# tdt_rereference.net
KiCad netlist of a schematic drawn in EAGLE
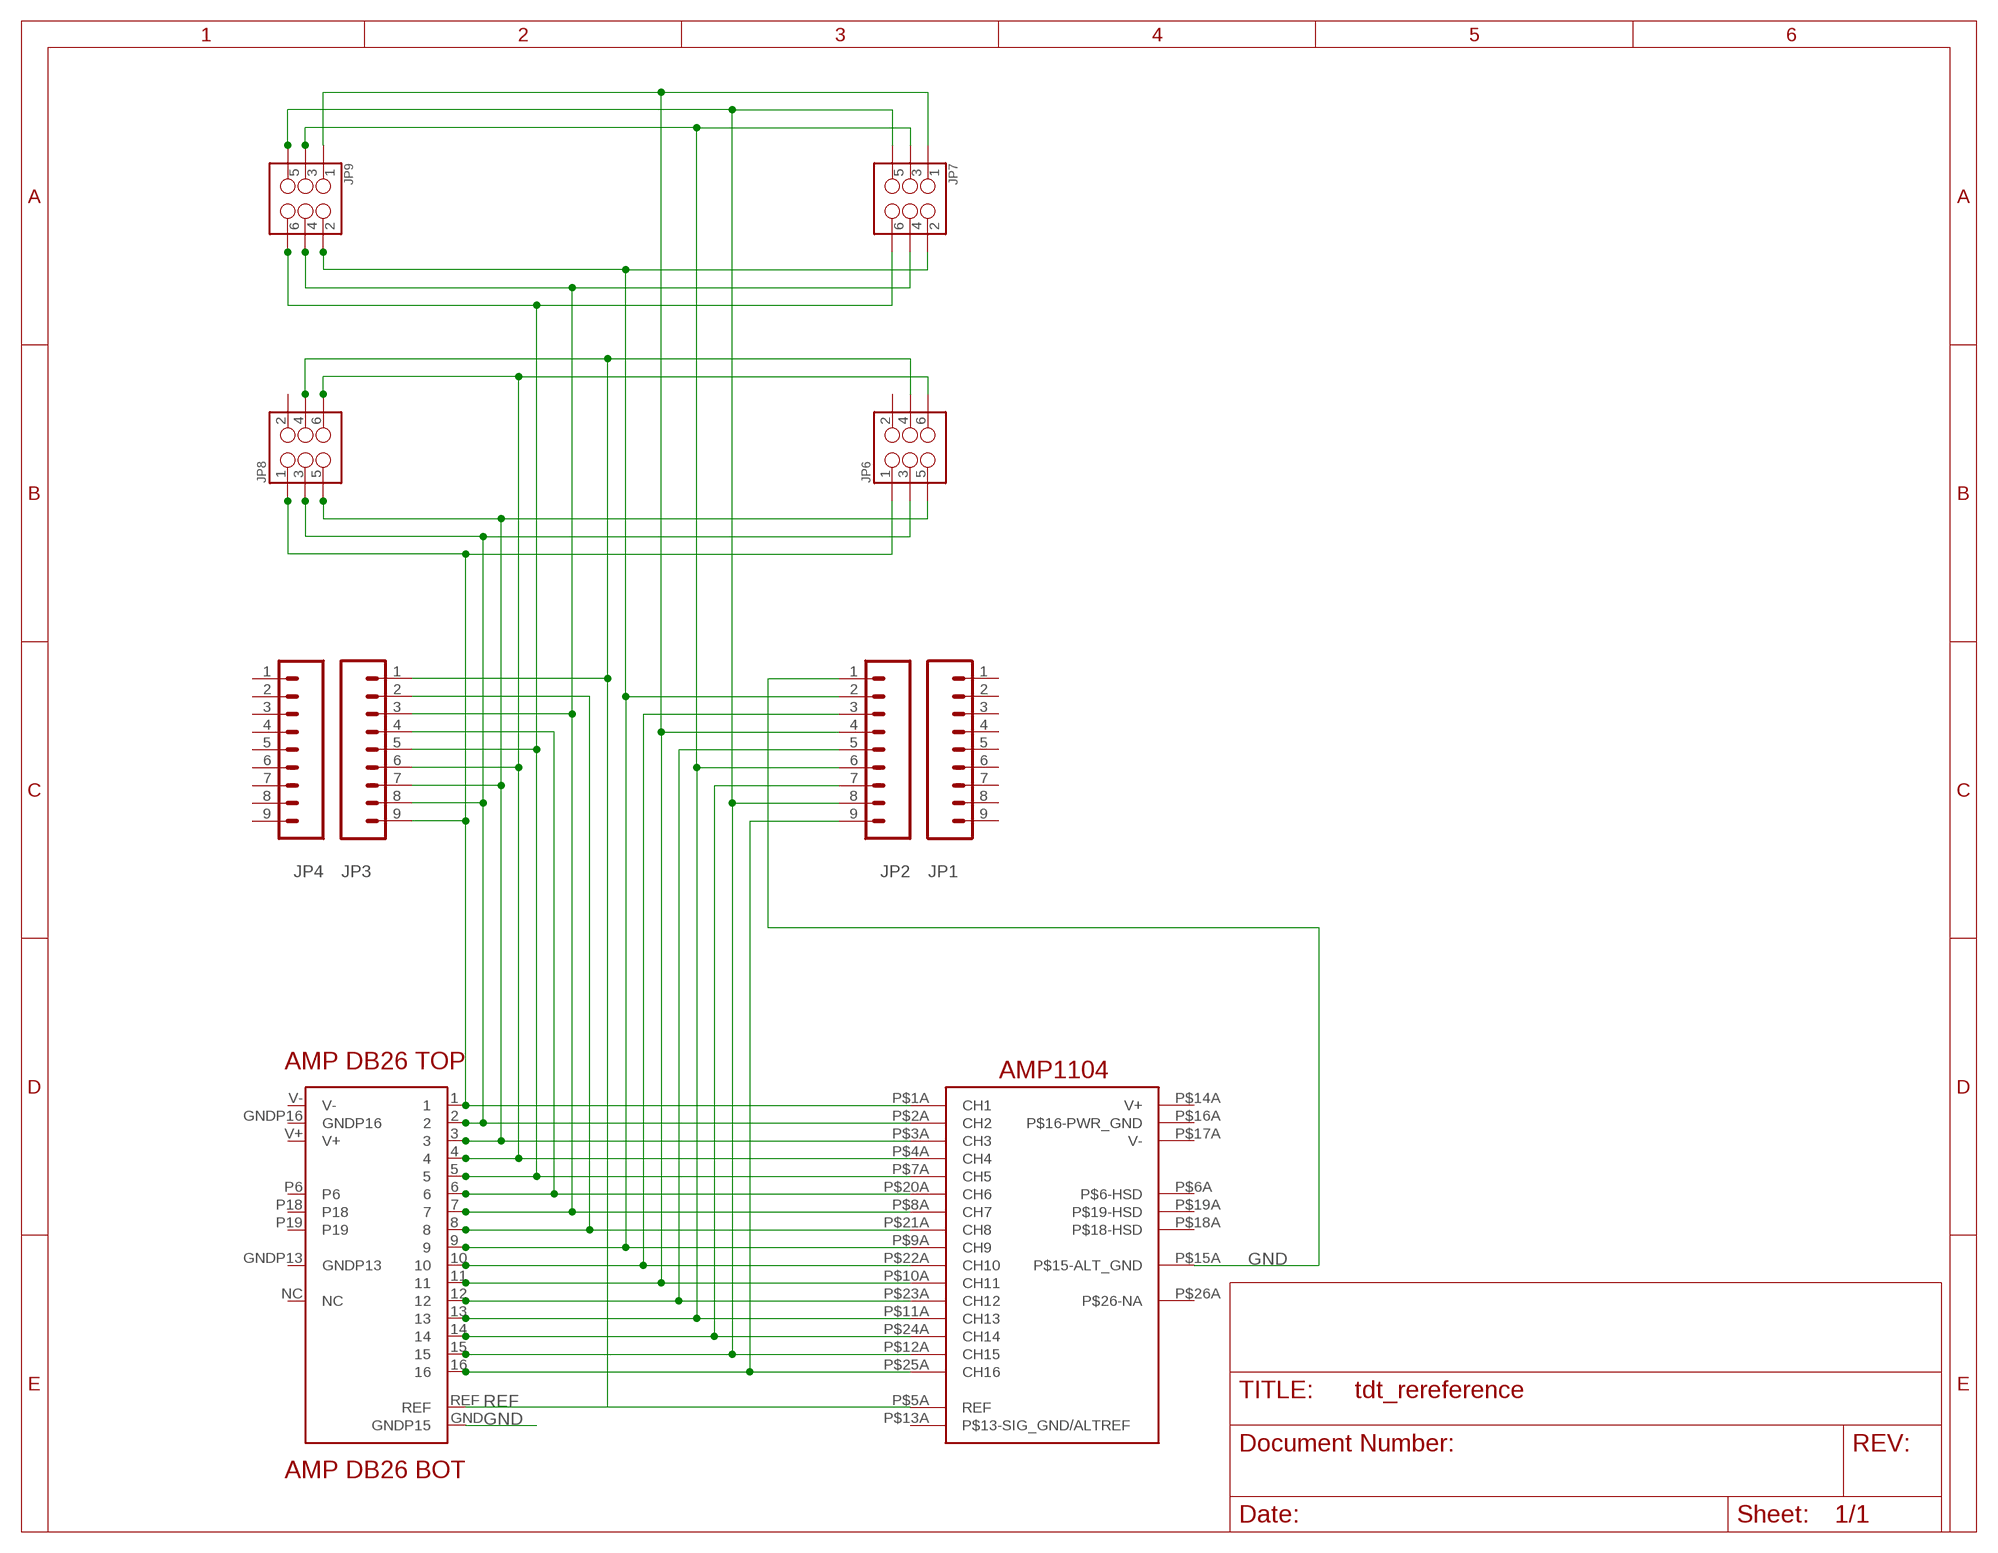
[diagram p0: schematic, sheet 1]

(export (version "E")
  (design (tool "Eeschema 10.0.6"))
  (components
    (comp (ref "JP1")
      (value "M09")
      (footprint "eagle-import:1X09")
      (libsource (lib "eagle-import") (part "M09"))
    )
    (comp (ref "JP2")
      (value "M09")
      (footprint "eagle-import:1X09")
      (libsource (lib "eagle-import") (part "M09"))
    )
    (comp (ref "JP3")
      (value "M09")
      (footprint "eagle-import:1X09")
      (libsource (lib "eagle-import") (part "M09"))
    )
    (comp (ref "JP4")
      (value "M09")
      (footprint "eagle-import:1X09")
      (libsource (lib "eagle-import") (part "M09"))
    )
    (comp (ref "JP6")
      (value "M03X22X3_SILK_MALE_PTH")
      (footprint "eagle-import:2X3")
      (libsource (lib "eagle-import") (part "M03X22X3_SILK_MALE_PTH"))
    )
    (comp (ref "JP7")
      (value "M03X22X3_SILK_MALE_PTH")
      (footprint "eagle-import:2X3")
      (libsource (lib "eagle-import") (part "M03X22X3_SILK_MALE_PTH"))
    )
    (comp (ref "JP8")
      (value "M03X22X3_SILK_MALE_PTH")
      (footprint "eagle-import:2X3")
      (libsource (lib "eagle-import") (part "M03X22X3_SILK_MALE_PTH"))
    )
    (comp (ref "JP9")
      (value "M03X22X3_SILK_MALE_PTH")
      (footprint "eagle-import:2X3")
      (libsource (lib "eagle-import") (part "M03X22X3_SILK_MALE_PTH"))
    )
    (comp (ref "U$1")
      (value "DB26-MALE-BOT")
      (footprint "eagle-import:DB26-MALE-BOT")
      (libsource (lib "eagle-import") (part "DB26-MALE-BOT"))
    )
    (comp (ref "U$2")
      (value "DB26-MALE-TOP")
      (footprint "eagle-import:DB26-MALE-TOP")
      (libsource (lib "eagle-import") (part "DB26-MALE-TOP"))
    )
    (comp (ref "U$3")
      (value "AMP1104")
      (footprint "eagle-import:AMP1104")
      (libsource (lib "eagle-import") (part "AMP1104"))
    )
  )
  (nets
    (net (code "1") (name "/GND") (class "Default")
      (node (ref "JP2") (pin "1") (pinfunction "1_1") (pintype "passive"))
      (node (ref "U$1") (pin "GND") (pinfunction "GNDP15_GND") (pintype "bidirectional"))
      (node (ref "U$3") (pin "P$15A") (pinfunction "P$15-ALT_GND_P$15A") (pintype "bidirectional"))
    )
    (net (code "2") (name "/REF") (class "Default")
      (node (ref "JP3") (pin "1") (pinfunction "1_1") (pintype "passive"))
      (node (ref "JP6") (pin "4") (pinfunction "4_4") (pintype "bidirectional"))
      (node (ref "JP8") (pin "4") (pinfunction "4_4") (pintype "bidirectional"))
      (node (ref "U$2") (pin "REF") (pinfunction "REF_REF") (pintype "bidirectional"))
      (node (ref "U$3") (pin "P$5A") (pinfunction "REF_P$5A") (pintype "bidirectional"))
    )
    (net (code "3") (name "Net-(U$3-CH1)") (class "Default")
      (node (ref "JP3") (pin "9") (pinfunction "9_9") (pintype "passive"))
      (node (ref "JP6") (pin "1") (pinfunction "1_1") (pintype "bidirectional"))
      (node (ref "JP8") (pin "1") (pinfunction "1_1") (pintype "bidirectional"))
      (node (ref "U$2") (pin "1") (pinfunction "1_1") (pintype "bidirectional"))
      (node (ref "U$3") (pin "P$1A") (pinfunction "CH1_P$1A") (pintype "bidirectional"))
    )
    (net (code "4") (name "Net-(U$3-CH2)") (class "Default")
      (node (ref "JP3") (pin "8") (pinfunction "8_8") (pintype "passive"))
      (node (ref "JP6") (pin "3") (pinfunction "3_3") (pintype "bidirectional"))
      (node (ref "JP8") (pin "3") (pinfunction "3_3") (pintype "bidirectional"))
      (node (ref "U$2") (pin "2") (pinfunction "2_2") (pintype "bidirectional"))
      (node (ref "U$3") (pin "P$2A") (pinfunction "CH2_P$2A") (pintype "bidirectional"))
    )
    (net (code "5") (name "Net-(U$3-CH3)") (class "Default")
      (node (ref "JP3") (pin "7") (pinfunction "7_7") (pintype "passive"))
      (node (ref "JP6") (pin "5") (pinfunction "5_5") (pintype "bidirectional"))
      (node (ref "JP8") (pin "5") (pinfunction "5_5") (pintype "bidirectional"))
      (node (ref "U$2") (pin "3") (pinfunction "3_3") (pintype "bidirectional"))
      (node (ref "U$3") (pin "P$3A") (pinfunction "CH3_P$3A") (pintype "bidirectional"))
    )
    (net (code "6") (name "Net-(U$3-CH4)") (class "Default")
      (node (ref "JP3") (pin "6") (pinfunction "6_6") (pintype "passive"))
      (node (ref "JP6") (pin "6") (pinfunction "6_6") (pintype "bidirectional"))
      (node (ref "JP8") (pin "6") (pinfunction "6_6") (pintype "bidirectional"))
      (node (ref "U$2") (pin "4") (pinfunction "4_4") (pintype "bidirectional"))
      (node (ref "U$3") (pin "P$4A") (pinfunction "CH4_P$4A") (pintype "bidirectional"))
    )
    (net (code "7") (name "Net-(U$3-CH5)") (class "Default")
      (node (ref "JP3") (pin "5") (pinfunction "5_5") (pintype "passive"))
      (node (ref "JP7") (pin "6") (pinfunction "6_6") (pintype "bidirectional"))
      (node (ref "JP9") (pin "6") (pinfunction "6_6") (pintype "bidirectional"))
      (node (ref "U$2") (pin "5") (pinfunction "5_5") (pintype "bidirectional"))
      (node (ref "U$3") (pin "P$7A") (pinfunction "CH5_P$7A") (pintype "bidirectional"))
    )
    (net (code "8") (name "Net-(U$3-CH6)") (class "Default")
      (node (ref "JP3") (pin "4") (pinfunction "4_4") (pintype "passive"))
      (node (ref "U$1") (pin "6") (pinfunction "6_6") (pintype "bidirectional"))
      (node (ref "U$3") (pin "P$20A") (pinfunction "CH6_P$20A") (pintype "bidirectional"))
    )
    (net (code "9") (name "Net-(U$3-CH7)") (class "Default")
      (node (ref "JP3") (pin "3") (pinfunction "3_3") (pintype "passive"))
      (node (ref "JP7") (pin "4") (pinfunction "4_4") (pintype "bidirectional"))
      (node (ref "JP9") (pin "4") (pinfunction "4_4") (pintype "bidirectional"))
      (node (ref "U$2") (pin "7") (pinfunction "7_7") (pintype "bidirectional"))
      (node (ref "U$3") (pin "P$8A") (pinfunction "CH7_P$8A") (pintype "bidirectional"))
    )
    (net (code "10") (name "Net-(U$3-CH8)") (class "Default")
      (node (ref "JP3") (pin "2") (pinfunction "2_2") (pintype "passive"))
      (node (ref "U$1") (pin "8") (pinfunction "8_8") (pintype "bidirectional"))
      (node (ref "U$3") (pin "P$21A") (pinfunction "CH8_P$21A") (pintype "bidirectional"))
    )
    (net (code "11") (name "Net-(U$3-CH9)") (class "Default")
      (node (ref "JP2") (pin "2") (pinfunction "2_2") (pintype "passive"))
      (node (ref "JP7") (pin "2") (pinfunction "2_2") (pintype "bidirectional"))
      (node (ref "JP9") (pin "2") (pinfunction "2_2") (pintype "bidirectional"))
      (node (ref "U$2") (pin "9") (pinfunction "9_9") (pintype "bidirectional"))
      (node (ref "U$3") (pin "P$9A") (pinfunction "CH9_P$9A") (pintype "bidirectional"))
    )
    (net (code "12") (name "Net-(U$3-CH10)") (class "Default")
      (node (ref "JP2") (pin "3") (pinfunction "3_3") (pintype "passive"))
      (node (ref "U$1") (pin "10") (pinfunction "10_10") (pintype "bidirectional"))
      (node (ref "U$3") (pin "P$22A") (pinfunction "CH10_P$22A") (pintype "bidirectional"))
    )
    (net (code "13") (name "Net-(U$3-CH11)") (class "Default")
      (node (ref "JP2") (pin "4") (pinfunction "4_4") (pintype "passive"))
      (node (ref "JP7") (pin "1") (pinfunction "1_1") (pintype "bidirectional"))
      (node (ref "JP9") (pin "1") (pinfunction "1_1") (pintype "bidirectional"))
      (node (ref "U$2") (pin "11") (pinfunction "11_11") (pintype "bidirectional"))
      (node (ref "U$3") (pin "P$10A") (pinfunction "CH11_P$10A") (pintype "bidirectional"))
    )
    (net (code "14") (name "Net-(U$3-CH12)") (class "Default")
      (node (ref "JP2") (pin "5") (pinfunction "5_5") (pintype "passive"))
      (node (ref "U$1") (pin "12") (pinfunction "12_12") (pintype "bidirectional"))
      (node (ref "U$3") (pin "P$23A") (pinfunction "CH12_P$23A") (pintype "bidirectional"))
    )
    (net (code "15") (name "Net-(U$3-CH13)") (class "Default")
      (node (ref "JP2") (pin "6") (pinfunction "6_6") (pintype "passive"))
      (node (ref "JP7") (pin "3") (pinfunction "3_3") (pintype "bidirectional"))
      (node (ref "JP9") (pin "3") (pinfunction "3_3") (pintype "bidirectional"))
      (node (ref "U$2") (pin "13") (pinfunction "13_13") (pintype "bidirectional"))
      (node (ref "U$3") (pin "P$11A") (pinfunction "CH13_P$11A") (pintype "bidirectional"))
    )
    (net (code "16") (name "Net-(U$3-CH14)") (class "Default")
      (node (ref "JP2") (pin "7") (pinfunction "7_7") (pintype "passive"))
      (node (ref "U$1") (pin "14") (pinfunction "14_14") (pintype "bidirectional"))
      (node (ref "U$3") (pin "P$24A") (pinfunction "CH14_P$24A") (pintype "bidirectional"))
    )
    (net (code "17") (name "Net-(U$3-CH15)") (class "Default")
      (node (ref "JP2") (pin "8") (pinfunction "8_8") (pintype "passive"))
      (node (ref "JP7") (pin "5") (pinfunction "5_5") (pintype "bidirectional"))
      (node (ref "JP9") (pin "5") (pinfunction "5_5") (pintype "bidirectional"))
      (node (ref "U$2") (pin "15") (pinfunction "15_15") (pintype "bidirectional"))
      (node (ref "U$3") (pin "P$12A") (pinfunction "CH15_P$12A") (pintype "bidirectional"))
    )
    (net (code "18") (name "Net-(U$3-CH16)") (class "Default")
      (node (ref "JP2") (pin "9") (pinfunction "9_9") (pintype "passive"))
      (node (ref "U$1") (pin "16") (pinfunction "16_16") (pintype "bidirectional"))
      (node (ref "U$3") (pin "P$25A") (pinfunction "CH16_P$25A") (pintype "bidirectional"))
    )
    (net (code "19") (name "unconnected-(JP1-Pad1)") (class "Default")
      (node (ref "JP1") (pin "1") (pinfunction "1_1") (pintype "passive"))
    )
    (net (code "20") (name "unconnected-(JP1-Pad2)") (class "Default")
      (node (ref "JP1") (pin "2") (pinfunction "2_2") (pintype "passive"))
    )
    (net (code "21") (name "unconnected-(JP1-Pad3)") (class "Default")
      (node (ref "JP1") (pin "3") (pinfunction "3_3") (pintype "passive"))
    )
    (net (code "22") (name "unconnected-(JP1-Pad4)") (class "Default")
      (node (ref "JP1") (pin "4") (pinfunction "4_4") (pintype "passive"))
    )
    (net (code "23") (name "unconnected-(JP1-Pad5)") (class "Default")
      (node (ref "JP1") (pin "5") (pinfunction "5_5") (pintype "passive"))
    )
    (net (code "24") (name "unconnected-(JP1-Pad6)") (class "Default")
      (node (ref "JP1") (pin "6") (pinfunction "6_6") (pintype "passive"))
    )
    (net (code "25") (name "unconnected-(JP1-Pad7)") (class "Default")
      (node (ref "JP1") (pin "7") (pinfunction "7_7") (pintype "passive"))
    )
    (net (code "26") (name "unconnected-(JP1-Pad8)") (class "Default")
      (node (ref "JP1") (pin "8") (pinfunction "8_8") (pintype "passive"))
    )
    (net (code "27") (name "unconnected-(JP1-Pad9)") (class "Default")
      (node (ref "JP1") (pin "9") (pinfunction "9_9") (pintype "passive"))
    )
    (net (code "28") (name "unconnected-(JP4-Pad1)") (class "Default")
      (node (ref "JP4") (pin "1") (pinfunction "1_1") (pintype "passive"))
    )
    (net (code "29") (name "unconnected-(JP4-Pad2)") (class "Default")
      (node (ref "JP4") (pin "2") (pinfunction "2_2") (pintype "passive"))
    )
    (net (code "30") (name "unconnected-(JP4-Pad3)") (class "Default")
      (node (ref "JP4") (pin "3") (pinfunction "3_3") (pintype "passive"))
    )
    (net (code "31") (name "unconnected-(JP4-Pad4)") (class "Default")
      (node (ref "JP4") (pin "4") (pinfunction "4_4") (pintype "passive"))
    )
    (net (code "32") (name "unconnected-(JP4-Pad5)") (class "Default")
      (node (ref "JP4") (pin "5") (pinfunction "5_5") (pintype "passive"))
    )
    (net (code "33") (name "unconnected-(JP4-Pad6)") (class "Default")
      (node (ref "JP4") (pin "6") (pinfunction "6_6") (pintype "passive"))
    )
    (net (code "34") (name "unconnected-(JP4-Pad7)") (class "Default")
      (node (ref "JP4") (pin "7") (pinfunction "7_7") (pintype "passive"))
    )
    (net (code "35") (name "unconnected-(JP4-Pad8)") (class "Default")
      (node (ref "JP4") (pin "8") (pinfunction "8_8") (pintype "passive"))
    )
    (net (code "36") (name "unconnected-(JP4-Pad9)") (class "Default")
      (node (ref "JP4") (pin "9") (pinfunction "9_9") (pintype "passive"))
    )
    (net (code "37") (name "unconnected-(JP6-Pad2)") (class "Default")
      (node (ref "JP6") (pin "2") (pinfunction "2_2") (pintype "bidirectional"))
    )
    (net (code "38") (name "unconnected-(JP8-Pad2)") (class "Default")
      (node (ref "JP8") (pin "2") (pinfunction "2_2") (pintype "bidirectional"))
    )
    (net (code "39") (name "unconnected-(U$1-PadGNDP16)") (class "Default")
      (node (ref "U$1") (pin "GNDP16") (pinfunction "GNDP16_GNDP16") (pintype "bidirectional"))
    )
    (net (code "40") (name "unconnected-(U$1-PadNC)") (class "Default")
      (node (ref "U$1") (pin "NC") (pinfunction "NC_NC") (pintype "bidirectional"))
    )
    (net (code "41") (name "unconnected-(U$1-PadP18)") (class "Default")
      (node (ref "U$1") (pin "P18") (pinfunction "P18_P18") (pintype "bidirectional"))
    )
    (net (code "42") (name "unconnected-(U$1-PadP19)") (class "Default")
      (node (ref "U$1") (pin "P19") (pinfunction "P19_P19") (pintype "bidirectional"))
    )
    (net (code "43") (name "unconnected-(U$1-PadV+)") (class "Default")
      (node (ref "U$1") (pin "V+") (pinfunction "V+_V+") (pintype "bidirectional"))
    )
    (net (code "44") (name "unconnected-(U$1-PadV-)") (class "Default")
      (node (ref "U$1") (pin "V-") (pinfunction "V-_V-") (pintype "bidirectional"))
    )
    (net (code "45") (name "unconnected-(U$2-PadGNDP13)") (class "Default")
      (node (ref "U$2") (pin "GNDP13") (pinfunction "GNDP13_GNDP13") (pintype "bidirectional"))
    )
    (net (code "46") (name "unconnected-(U$2-PadP6)") (class "Default")
      (node (ref "U$2") (pin "P6") (pinfunction "P6_P6") (pintype "bidirectional"))
    )
    (net (code "47") (name "unconnected-(U$3-P$6-HSD-PadP$6A)") (class "Default")
      (node (ref "U$3") (pin "P$6A") (pinfunction "P$6-HSD_P$6A") (pintype "bidirectional"))
    )
    (net (code "48") (name "unconnected-(U$3-P$13-SIG_GND{slash}ALTREF-PadP$13A)") (class "Default")
      (node (ref "U$3") (pin "P$13A") (pinfunction "P$13-SIG_GND/ALTREF_P$13A") (pintype "bidirectional"))
    )
    (net (code "49") (name "unconnected-(U$3-P$16-PWR_GND-PadP$16A)") (class "Default")
      (node (ref "U$3") (pin "P$16A") (pinfunction "P$16-PWR_GND_P$16A") (pintype "bidirectional"))
    )
    (net (code "50") (name "unconnected-(U$3-P$18-HSD-PadP$18A)") (class "Default")
      (node (ref "U$3") (pin "P$18A") (pinfunction "P$18-HSD_P$18A") (pintype "bidirectional"))
    )
    (net (code "51") (name "unconnected-(U$3-P$19-HSD-PadP$19A)") (class "Default")
      (node (ref "U$3") (pin "P$19A") (pinfunction "P$19-HSD_P$19A") (pintype "bidirectional"))
    )
    (net (code "52") (name "unconnected-(U$3-P$26-NA-PadP$26A)") (class "Default")
      (node (ref "U$3") (pin "P$26A") (pinfunction "P$26-NA_P$26A") (pintype "bidirectional"))
    )
    (net (code "53") (name "unconnected-(U$3-V+-PadP$14A)") (class "Default")
      (node (ref "U$3") (pin "P$14A") (pinfunction "V+_P$14A") (pintype "bidirectional"))
    )
    (net (code "54") (name "unconnected-(U$3-V--PadP$17A)") (class "Default")
      (node (ref "U$3") (pin "P$17A") (pinfunction "V-_P$17A") (pintype "bidirectional"))
    )
  )
)
